# batt_mon_v1.net
KiCad netlist of a schematic drawn in EAGLE
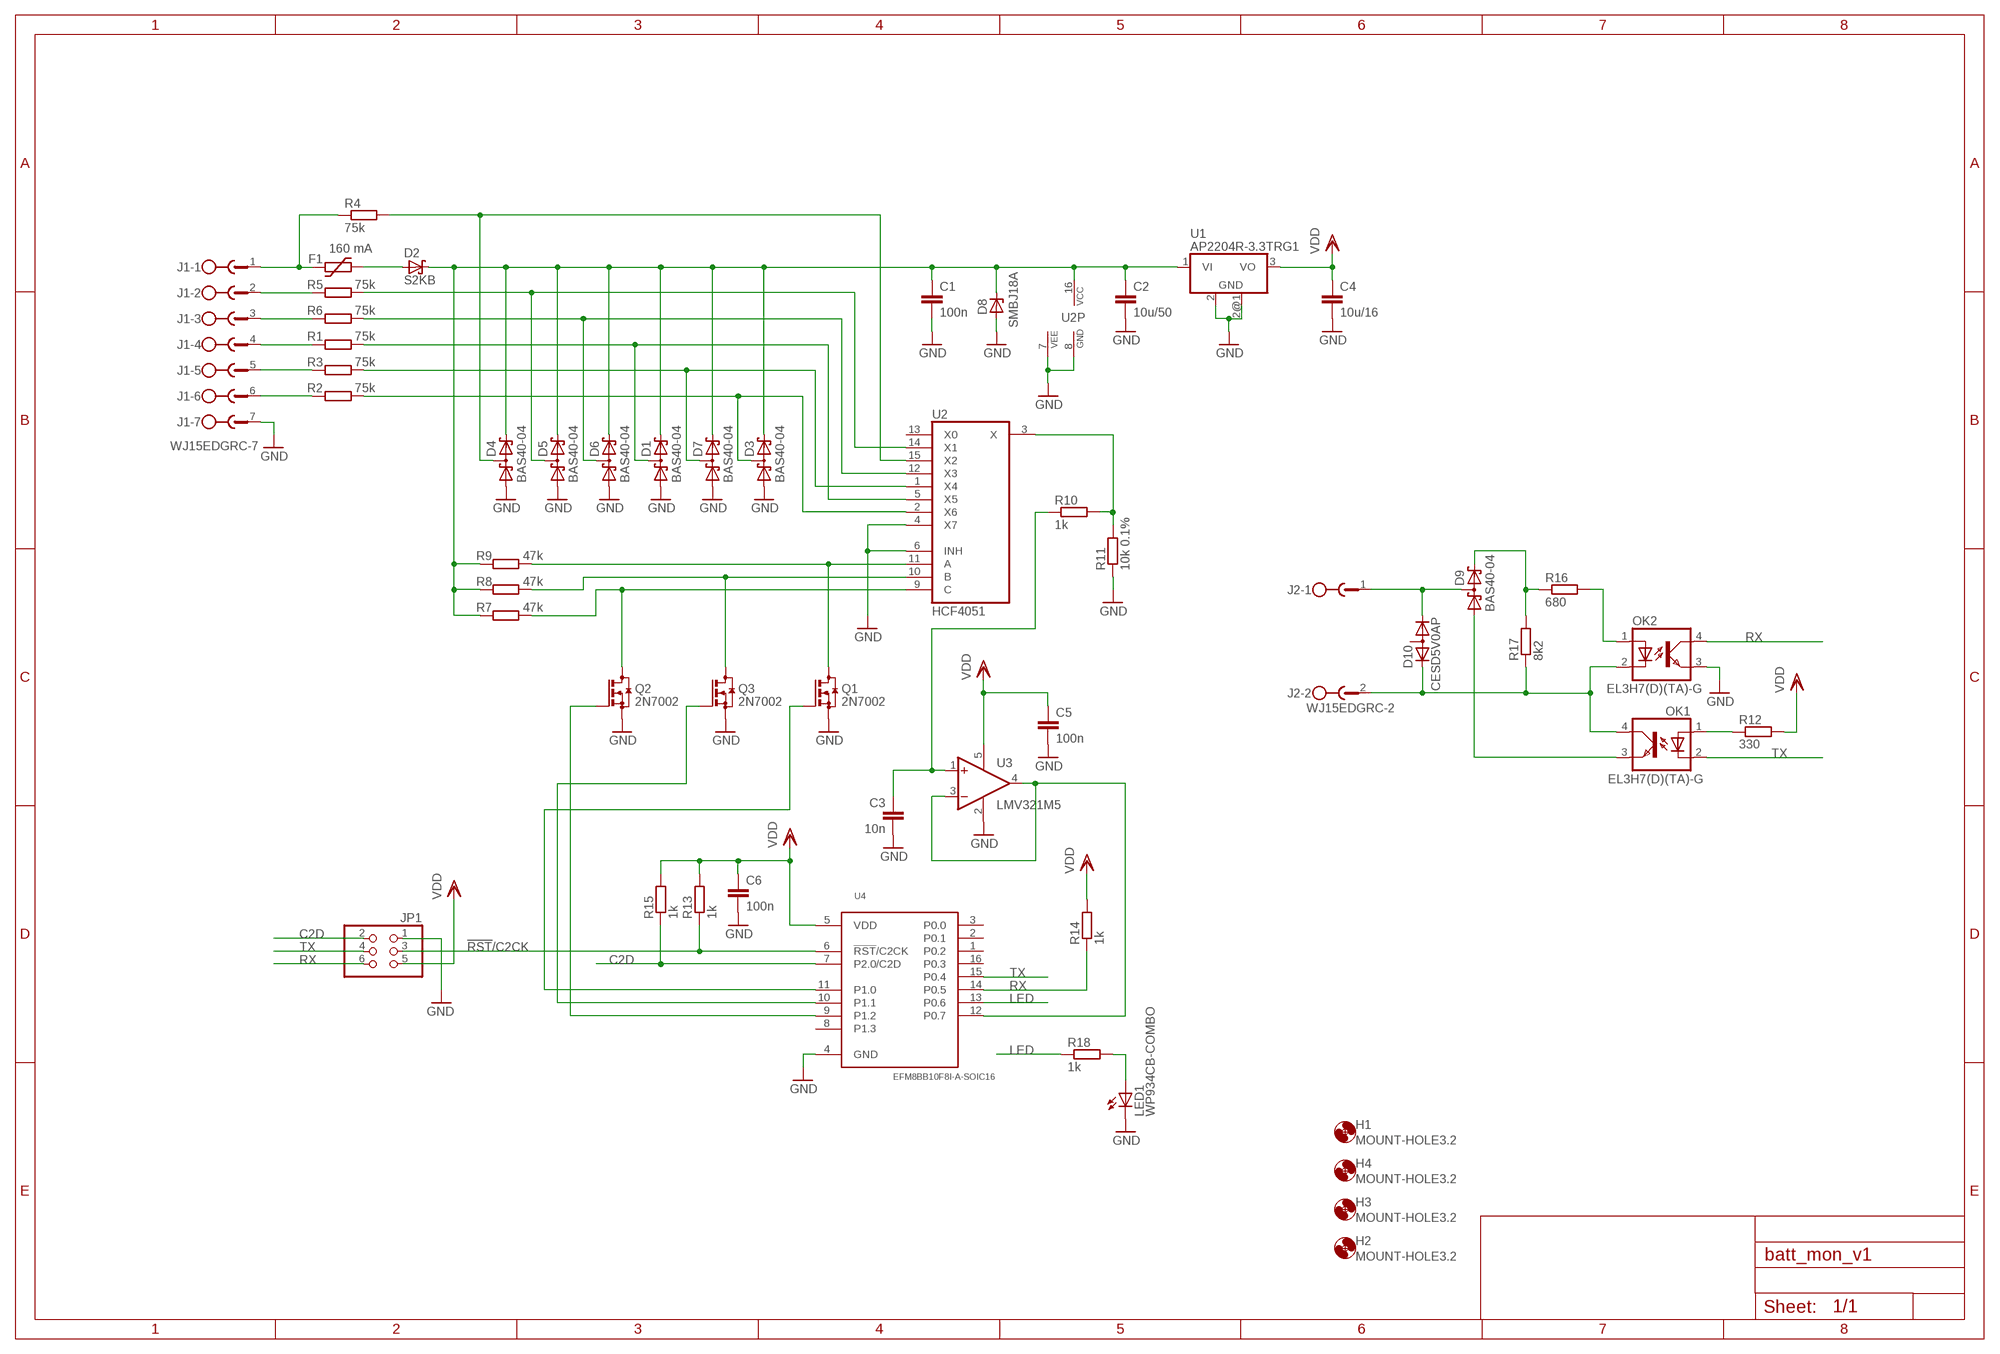
[diagram p0: schematic, sheet 1]

(export (version "E")
  (design (tool "Eeschema 10.0.6"))
  (components
    (comp (ref "C1")
      (value "100n")
      (footprint "eagle-import:C0805")
      (libsource (lib "eagle-import") (part "C-EUC0805"))
    )
    (comp (ref "C2")
      (value "10u/50")
      (footprint "eagle-import:C1206")
      (libsource (lib "eagle-import") (part "C-EUC1206"))
    )
    (comp (ref "C3")
      (value "10n")
      (footprint "eagle-import:C0805")
      (libsource (lib "eagle-import") (part "C-EUC0805"))
    )
    (comp (ref "C4")
      (value "10u/16")
      (footprint "eagle-import:C1206")
      (libsource (lib "eagle-import") (part "C-EUC1206"))
    )
    (comp (ref "C5")
      (value "100n")
      (footprint "eagle-import:C0805")
      (libsource (lib "eagle-import") (part "C-EUC0805"))
    )
    (comp (ref "C6")
      (value "100n")
      (footprint "eagle-import:C0805")
      (libsource (lib "eagle-import") (part "C-EUC0805"))
    )
    (comp (ref "D1")
      (value "BAS40-04")
      (footprint "eagle-import:SOT23")
      (libsource (lib "eagle-import") (part "BAS40-04"))
    )
    (comp (ref "D2")
      (value "S2KB")
      (footprint "eagle-import:SMB")
      (libsource (lib "eagle-import") (part "SCHOTTKY-DIODESMD"))
    )
    (comp (ref "D3")
      (value "BAS40-04")
      (footprint "eagle-import:SOT23")
      (libsource (lib "eagle-import") (part "BAS40-04"))
    )
    (comp (ref "D4")
      (value "BAS40-04")
      (footprint "eagle-import:SOT23")
      (libsource (lib "eagle-import") (part "BAS40-04"))
    )
    (comp (ref "D5")
      (value "BAS40-04")
      (footprint "eagle-import:SOT23")
      (libsource (lib "eagle-import") (part "BAS40-04"))
    )
    (comp (ref "D6")
      (value "BAS40-04")
      (footprint "eagle-import:SOT23")
      (libsource (lib "eagle-import") (part "BAS40-04"))
    )
    (comp (ref "D7")
      (value "BAS40-04")
      (footprint "eagle-import:SOT23")
      (libsource (lib "eagle-import") (part "BAS40-04"))
    )
    (comp (ref "D8")
      (value "SMBJ18A")
      (footprint "eagle-import:SMB")
      (libsource (lib "eagle-import") (part "ZENER-DIODESMB"))
    )
    (comp (ref "D9")
      (value "BAS40-04")
      (footprint "eagle-import:SOT23")
      (libsource (lib "eagle-import") (part "BAS40-04"))
    )
    (comp (ref "D10")
      (value "CESD5V0AP")
      (footprint "eagle-import:SOT23")
      (libsource (lib "eagle-import") (part "DIODE-2CA|ACSOT23"))
    )
    (comp (ref "F1")
      (value "160 mA")
      (footprint "eagle-import:1206L")
      (libsource (lib "eagle-import") (part "1206L"))
    )
    (comp (ref "H1")
      (value "MOUNT-HOLE3.2")
      (footprint "eagle-import:3,2")
      (libsource (lib "eagle-import") (part "MOUNT-HOLE3.2"))
    )
    (comp (ref "H2")
      (value "MOUNT-HOLE3.2")
      (footprint "eagle-import:3,2")
      (libsource (lib "eagle-import") (part "MOUNT-HOLE3.2"))
    )
    (comp (ref "H3")
      (value "MOUNT-HOLE3.2")
      (footprint "eagle-import:3,2")
      (libsource (lib "eagle-import") (part "MOUNT-HOLE3.2"))
    )
    (comp (ref "H4")
      (value "MOUNT-HOLE3.2")
      (footprint "eagle-import:3,2")
      (libsource (lib "eagle-import") (part "MOUNT-HOLE3.2"))
    )
    (comp (ref "J1")
      (value "WJ15EDGRC-7")
      (footprint "eagle-import:WJ15EDGRC-3.81-7")
      (libsource (lib "eagle-import") (part "WJ15EDGRC-7"))
    )
    (comp (ref "J2")
      (value "WJ15EDGRC-2")
      (footprint "eagle-import:WJ15EDGRC-3.81-2")
      (libsource (lib "eagle-import") (part "WJ15EDGRC-2"))
    )
    (comp (ref "JP1")
      (value "PINHD-2X3")
      (footprint "eagle-import:2X03")
      (libsource (lib "eagle-import") (part "PINHD-2X3"))
    )
    (comp (ref "LED1")
      (value "WP934CB-COMBO")
      (footprint "eagle-import:WP934CB-COMBO")
      (libsource (lib "eagle-import") (part "WP934CB-COMBO"))
    )
    (comp (ref "OK1")
      (value "EL3H7(D)(TA)-G")
      (footprint "eagle-import:MINI-FLAT-4")
      (libsource (lib "eagle-import") (part "EL3H7"))
    )
    (comp (ref "OK2")
      (value "EL3H7(D)(TA)-G")
      (footprint "eagle-import:MINI-FLAT-4")
      (libsource (lib "eagle-import") (part "EL3H7"))
    )
    (comp (ref "Q1")
      (value "2N7002")
      (footprint "eagle-import:SOT23")
      (libsource (lib "eagle-import") (part "BSS123"))
    )
    (comp (ref "Q2")
      (value "2N7002")
      (footprint "eagle-import:SOT23")
      (libsource (lib "eagle-import") (part "BSS123"))
    )
    (comp (ref "Q3")
      (value "2N7002")
      (footprint "eagle-import:SOT23")
      (libsource (lib "eagle-import") (part "BSS123"))
    )
    (comp (ref "R1")
      (value "75k")
      (footprint "eagle-import:R1206")
      (libsource (lib "eagle-import") (part "R-EU_R1206"))
    )
    (comp (ref "R2")
      (value "75k")
      (footprint "eagle-import:R1206")
      (libsource (lib "eagle-import") (part "R-EU_R1206"))
    )
    (comp (ref "R3")
      (value "75k")
      (footprint "eagle-import:R1206")
      (libsource (lib "eagle-import") (part "R-EU_R1206"))
    )
    (comp (ref "R4")
      (value "75k")
      (footprint "eagle-import:R1206")
      (libsource (lib "eagle-import") (part "R-EU_R1206"))
    )
    (comp (ref "R5")
      (value "75k")
      (footprint "eagle-import:R1206")
      (libsource (lib "eagle-import") (part "R-EU_R1206"))
    )
    (comp (ref "R6")
      (value "75k")
      (footprint "eagle-import:R1206")
      (libsource (lib "eagle-import") (part "R-EU_R1206"))
    )
    (comp (ref "R7")
      (value "47k")
      (footprint "eagle-import:R0805")
      (libsource (lib "eagle-import") (part "R-EU_R0805"))
    )
    (comp (ref "R8")
      (value "47k")
      (footprint "eagle-import:R0805")
      (libsource (lib "eagle-import") (part "R-EU_R0805"))
    )
    (comp (ref "R9")
      (value "47k")
      (footprint "eagle-import:R0805")
      (libsource (lib "eagle-import") (part "R-EU_R0805"))
    )
    (comp (ref "R10")
      (value "1k")
      (footprint "eagle-import:R0805")
      (libsource (lib "eagle-import") (part "R-EU_R0805"))
    )
    (comp (ref "R11")
      (value "10k 0.1%")
      (footprint "eagle-import:R0805")
      (libsource (lib "eagle-import") (part "R-EU_R0805"))
    )
    (comp (ref "R12")
      (value "330")
      (footprint "eagle-import:R0805")
      (libsource (lib "eagle-import") (part "R-EU_R0805"))
    )
    (comp (ref "R13")
      (value "1k")
      (footprint "eagle-import:R0805")
      (libsource (lib "eagle-import") (part "R-EU_R0805"))
    )
    (comp (ref "R14")
      (value "1k")
      (footprint "eagle-import:R0805")
      (libsource (lib "eagle-import") (part "R-EU_R0805"))
    )
    (comp (ref "R15")
      (value "1k")
      (footprint "eagle-import:R0805")
      (libsource (lib "eagle-import") (part "R-EU_R0805"))
    )
    (comp (ref "R16")
      (value "680")
      (footprint "eagle-import:R0805")
      (libsource (lib "eagle-import") (part "R-EU_R0805"))
    )
    (comp (ref "R17")
      (value "8k2")
      (footprint "eagle-import:R0805")
      (libsource (lib "eagle-import") (part "R-EU_R0805"))
    )
    (comp (ref "R18")
      (value "1k")
      (footprint "eagle-import:R0805")
      (libsource (lib "eagle-import") (part "R-EU_R0805"))
    )
    (comp (ref "U1")
      (value "AP2204R-3.3TRG1")
      (footprint "eagle-import:SOT89")
      (libsource (lib "eagle-import") (part "MCP1754MB33"))
    )
    (comp (ref "U2")
      (value "HCF4051")
      (footprint "eagle-import:SO16")
      (libsource (lib "eagle-import") (part "4051D"))
    )
    (comp (ref "U3")
      (value "LMV321M5")
      (footprint "eagle-import:SOT23-5")
      (libsource (lib "eagle-import") (part "LMV321?M5"))
    )
    (comp (ref "U4")
      (value "EFM8BB10F8I-A-SOIC16")
      (footprint "eagle-import:SO16")
      (libsource (lib "eagle-import") (part "EFM8BB1"))
    )
  )
  (nets
    (net (code "1") (name "/C2D") (class "Default")
      (node (ref "JP1") (pin "2") (pinfunction "2_2") (pintype "passive"))
      (node (ref "R15") (pin "1") (pinfunction "1_1") (pintype "passive"))
      (node (ref "U4") (pin "7") (pinfunction "P2.0/C2D_7") (pintype "bidirectional"))
    )
    (net (code "2") (name "/LED") (class "Default")
      (node (ref "R18") (pin "1") (pinfunction "1_1") (pintype "passive"))
      (node (ref "U4") (pin "13") (pinfunction "P0.6_13") (pintype "bidirectional"))
    )
    (net (code "3") (name "/RX") (class "Default")
      (node (ref "JP1") (pin "6") (pinfunction "6_6") (pintype "passive"))
      (node (ref "OK2") (pin "4") (pinfunction "COL_4") (pintype "passive"))
      (node (ref "R14") (pin "1") (pinfunction "1_1") (pintype "passive"))
      (node (ref "U4") (pin "14") (pinfunction "P0.5_14") (pintype "bidirectional"))
    )
    (net (code "4") (name "/TX") (class "Default")
      (node (ref "JP1") (pin "4") (pinfunction "4_4") (pintype "passive"))
      (node (ref "OK1") (pin "2") (pinfunction "C_2") (pintype "passive"))
      (node (ref "U4") (pin "15") (pinfunction "P0.4_15") (pintype "bidirectional"))
    )
    (net (code "5") (name "/~{RST}{slash}C2CK") (class "Default")
      (node (ref "JP1") (pin "3") (pinfunction "3_3") (pintype "passive"))
      (node (ref "R13") (pin "1") (pinfunction "1_1") (pintype "passive"))
      (node (ref "U4") (pin "6") (pinfunction "~{RST}/C2CK_6") (pintype "bidirectional"))
    )
    (net (code "6") (name "GND") (class "Default")
      (node (ref "C1") (pin "2") (pinfunction "2_2") (pintype "passive"))
      (node (ref "C2") (pin "2") (pinfunction "2_2") (pintype "passive"))
      (node (ref "C3") (pin "2") (pinfunction "2_2") (pintype "passive"))
      (node (ref "C4") (pin "2") (pinfunction "2_2") (pintype "passive"))
      (node (ref "C5") (pin "2") (pinfunction "2_2") (pintype "passive"))
      (node (ref "C6") (pin "2") (pinfunction "2_2") (pintype "passive"))
      (node (ref "D1") (pin "1") (pinfunction "A1_1") (pintype "passive"))
      (node (ref "D3") (pin "1") (pinfunction "A1_1") (pintype "passive"))
      (node (ref "D4") (pin "1") (pinfunction "A1_1") (pintype "passive"))
      (node (ref "D5") (pin "1") (pinfunction "A1_1") (pintype "passive"))
      (node (ref "D6") (pin "1") (pinfunction "A1_1") (pintype "passive"))
      (node (ref "D7") (pin "1") (pinfunction "A1_1") (pintype "passive"))
      (node (ref "D8") (pin "A") (pinfunction "A_A") (pintype "passive"))
      (node (ref "J1") (pin "7") (pinfunction "1_7") (pintype "passive"))
      (node (ref "JP1") (pin "1") (pinfunction "1_1") (pintype "passive"))
      (node (ref "LED1") (pin "K") (pinfunction "C_K") (pintype "passive"))
      (node (ref "LED1") (pin "K1") (pinfunction "C_K1") (pintype "passive"))
      (node (ref "OK2") (pin "3") (pinfunction "EMIT_3") (pintype "passive"))
      (node (ref "Q1") (pin "2") (pinfunction "S_2") (pintype "passive"))
      (node (ref "Q2") (pin "2") (pinfunction "S_2") (pintype "passive"))
      (node (ref "Q3") (pin "2") (pinfunction "S_2") (pintype "passive"))
      (node (ref "R11") (pin "1") (pinfunction "1_1") (pintype "passive"))
      (node (ref "U1") (pin "2") (pinfunction "GND_2") (pintype "passive"))
      (node (ref "U1") (pin "2@1") (pinfunction "GND_2@1") (pintype "passive"))
      (node (ref "U2") (pin "4") (pinfunction "X7_4") (pintype "bidirectional"))
      (node (ref "U2") (pin "6") (pinfunction "INH_6") (pintype "input"))
      (node (ref "U2") (pin "7") (pinfunction "VEE_7") (pintype "power_in"))
      (node (ref "U2") (pin "8") (pinfunction "GND_8") (pintype "power_in"))
      (node (ref "U3") (pin "2") (pinfunction "V-_2") (pintype "power_in"))
      (node (ref "U4") (pin "4") (pinfunction "GND_4") (pintype "bidirectional"))
    )
    (net (code "7") (name "Net-(D1-C1A2)") (class "Default")
      (node (ref "D1") (pin "3") (pinfunction "C1A2_3") (pintype "passive"))
      (node (ref "R1") (pin "2") (pinfunction "2_2") (pintype "passive"))
      (node (ref "U2") (pin "5") (pinfunction "X5_5") (pintype "bidirectional"))
    )
    (net (code "8") (name "Net-(D1-C2)") (class "Default")
      (node (ref "C1") (pin "1") (pinfunction "1_1") (pintype "passive"))
      (node (ref "C2") (pin "1") (pinfunction "1_1") (pintype "passive"))
      (node (ref "D1") (pin "2") (pinfunction "C2_2") (pintype "passive"))
      (node (ref "D2") (pin "C") (pinfunction "C_C") (pintype "passive"))
      (node (ref "D3") (pin "2") (pinfunction "C2_2") (pintype "passive"))
      (node (ref "D4") (pin "2") (pinfunction "C2_2") (pintype "passive"))
      (node (ref "D5") (pin "2") (pinfunction "C2_2") (pintype "passive"))
      (node (ref "D6") (pin "2") (pinfunction "C2_2") (pintype "passive"))
      (node (ref "D7") (pin "2") (pinfunction "C2_2") (pintype "passive"))
      (node (ref "D8") (pin "C") (pinfunction "C_C") (pintype "passive"))
      (node (ref "R7") (pin "1") (pinfunction "1_1") (pintype "passive"))
      (node (ref "R8") (pin "1") (pinfunction "1_1") (pintype "passive"))
      (node (ref "R9") (pin "1") (pinfunction "1_1") (pintype "passive"))
      (node (ref "U1") (pin "1") (pinfunction "VI_1") (pintype "input"))
      (node (ref "U2") (pin "16") (pinfunction "VCC_16") (pintype "power_in"))
    )
    (net (code "9") (name "Net-(D3-C1A2)") (class "Default")
      (node (ref "D3") (pin "3") (pinfunction "C1A2_3") (pintype "passive"))
      (node (ref "R2") (pin "2") (pinfunction "2_2") (pintype "passive"))
      (node (ref "U2") (pin "2") (pinfunction "X6_2") (pintype "bidirectional"))
    )
    (net (code "10") (name "Net-(D4-C1A2)") (class "Default")
      (node (ref "D4") (pin "3") (pinfunction "C1A2_3") (pintype "passive"))
      (node (ref "R4") (pin "2") (pinfunction "2_2") (pintype "passive"))
      (node (ref "U2") (pin "15") (pinfunction "X2_15") (pintype "bidirectional"))
    )
    (net (code "11") (name "Net-(D5-C1A2)") (class "Default")
      (node (ref "D5") (pin "3") (pinfunction "C1A2_3") (pintype "passive"))
      (node (ref "R5") (pin "2") (pinfunction "2_2") (pintype "passive"))
      (node (ref "U2") (pin "14") (pinfunction "X1_14") (pintype "bidirectional"))
    )
    (net (code "12") (name "Net-(D6-C1A2)") (class "Default")
      (node (ref "D6") (pin "3") (pinfunction "C1A2_3") (pintype "passive"))
      (node (ref "R6") (pin "2") (pinfunction "2_2") (pintype "passive"))
      (node (ref "U2") (pin "12") (pinfunction "X3_12") (pintype "bidirectional"))
    )
    (net (code "13") (name "Net-(D7-C1A2)") (class "Default")
      (node (ref "D7") (pin "3") (pinfunction "C1A2_3") (pintype "passive"))
      (node (ref "R3") (pin "2") (pinfunction "2_2") (pintype "passive"))
      (node (ref "U2") (pin "1") (pinfunction "X4_1") (pintype "bidirectional"))
    )
    (net (code "14") (name "Net-(D9-A1)") (class "Default")
      (node (ref "D9") (pin "1") (pinfunction "A1_1") (pintype "passive"))
      (node (ref "OK1") (pin "3") (pinfunction "EMIT_3") (pintype "passive"))
    )
    (net (code "15") (name "Net-(D9-C2)") (class "Default")
      (node (ref "D9") (pin "2") (pinfunction "C2_2") (pintype "passive"))
      (node (ref "R16") (pin "1") (pinfunction "1_1") (pintype "passive"))
      (node (ref "R17") (pin "2") (pinfunction "2_2") (pintype "passive"))
    )
    (net (code "16") (name "Net-(D10-K1)") (class "Default")
      (node (ref "D10") (pin "1") (pinfunction "K1_1") (pintype "passive"))
      (node (ref "D9") (pin "3") (pinfunction "C1A2_3") (pintype "passive"))
      (node (ref "J2") (pin "1") (pinfunction "1_1") (pintype "passive"))
    )
    (net (code "17") (name "Net-(D10-K2)") (class "Default")
      (node (ref "D10") (pin "2") (pinfunction "K2_2") (pintype "passive"))
      (node (ref "J2") (pin "2") (pinfunction "1_2") (pintype "passive"))
      (node (ref "OK1") (pin "4") (pinfunction "COL_4") (pintype "passive"))
      (node (ref "OK2") (pin "2") (pinfunction "C_2") (pintype "passive"))
      (node (ref "R17") (pin "1") (pinfunction "1_1") (pintype "passive"))
    )
    (net (code "18") (name "Net-(F1-1)") (class "Default")
      (node (ref "F1") (pin "P$1") (pinfunction "1_P$1") (pintype "passive"))
      (node (ref "J1") (pin "1") (pinfunction "1_1") (pintype "passive"))
      (node (ref "R4") (pin "1") (pinfunction "1_1") (pintype "passive"))
    )
    (net (code "19") (name "Net-(F1-2)") (class "Default")
      (node (ref "D2") (pin "A") (pinfunction "A_A") (pintype "passive"))
      (node (ref "F1") (pin "P$2") (pinfunction "2_P$2") (pintype "passive"))
    )
    (net (code "20") (name "Net-(J1B-1)") (class "Default")
      (node (ref "J1") (pin "2") (pinfunction "1_2") (pintype "passive"))
      (node (ref "R5") (pin "1") (pinfunction "1_1") (pintype "passive"))
    )
    (net (code "21") (name "Net-(J1C-1)") (class "Default")
      (node (ref "J1") (pin "3") (pinfunction "1_3") (pintype "passive"))
      (node (ref "R6") (pin "1") (pinfunction "1_1") (pintype "passive"))
    )
    (net (code "22") (name "Net-(J1D-1)") (class "Default")
      (node (ref "J1") (pin "4") (pinfunction "1_4") (pintype "passive"))
      (node (ref "R1") (pin "1") (pinfunction "1_1") (pintype "passive"))
    )
    (net (code "23") (name "Net-(J1E-1)") (class "Default")
      (node (ref "J1") (pin "5") (pinfunction "1_5") (pintype "passive"))
      (node (ref "R3") (pin "1") (pinfunction "1_1") (pintype "passive"))
    )
    (net (code "24") (name "Net-(J1F-1)") (class "Default")
      (node (ref "J1") (pin "6") (pinfunction "1_6") (pintype "passive"))
      (node (ref "R2") (pin "1") (pinfunction "1_1") (pintype "passive"))
    )
    (net (code "25") (name "Net-(LED1-A-PadA1)") (class "Default")
      (node (ref "LED1") (pin "A") (pinfunction "A_A") (pintype "passive"))
      (node (ref "LED1") (pin "A1") (pinfunction "A_A1") (pintype "passive"))
      (node (ref "R18") (pin "2") (pinfunction "2_2") (pintype "passive"))
    )
    (net (code "26") (name "Net-(OK1-A)") (class "Default")
      (node (ref "OK1") (pin "1") (pinfunction "A_1") (pintype "passive"))
      (node (ref "R12") (pin "1") (pinfunction "1_1") (pintype "passive"))
    )
    (net (code "27") (name "Net-(OK2-A)") (class "Default")
      (node (ref "OK2") (pin "1") (pinfunction "A_1") (pintype "passive"))
      (node (ref "R16") (pin "2") (pinfunction "2_2") (pintype "passive"))
    )
    (net (code "28") (name "Net-(Q1-D)") (class "Default")
      (node (ref "Q1") (pin "3") (pinfunction "D_3") (pintype "passive"))
      (node (ref "R9") (pin "2") (pinfunction "2_2") (pintype "passive"))
      (node (ref "U2") (pin "11") (pinfunction "A_11") (pintype "input"))
    )
    (net (code "29") (name "Net-(Q1-G)") (class "Default")
      (node (ref "Q1") (pin "1") (pinfunction "G_1") (pintype "passive"))
      (node (ref "U4") (pin "11") (pinfunction "P1.0_11") (pintype "bidirectional"))
    )
    (net (code "30") (name "Net-(Q2-D)") (class "Default")
      (node (ref "Q2") (pin "3") (pinfunction "D_3") (pintype "passive"))
      (node (ref "R7") (pin "2") (pinfunction "2_2") (pintype "passive"))
      (node (ref "U2") (pin "9") (pinfunction "C_9") (pintype "input"))
    )
    (net (code "31") (name "Net-(Q2-G)") (class "Default")
      (node (ref "Q2") (pin "1") (pinfunction "G_1") (pintype "passive"))
      (node (ref "U4") (pin "9") (pinfunction "P1.2_9") (pintype "bidirectional"))
    )
    (net (code "32") (name "Net-(Q3-D)") (class "Default")
      (node (ref "Q3") (pin "3") (pinfunction "D_3") (pintype "passive"))
      (node (ref "R8") (pin "2") (pinfunction "2_2") (pintype "passive"))
      (node (ref "U2") (pin "10") (pinfunction "B_10") (pintype "input"))
    )
    (net (code "33") (name "Net-(Q3-G)") (class "Default")
      (node (ref "Q3") (pin "1") (pinfunction "G_1") (pintype "passive"))
      (node (ref "U4") (pin "10") (pinfunction "P1.1_10") (pintype "bidirectional"))
    )
    (net (code "34") (name "Net-(U2A-X)") (class "Default")
      (node (ref "R10") (pin "2") (pinfunction "2_2") (pintype "passive"))
      (node (ref "R11") (pin "2") (pinfunction "2_2") (pintype "passive"))
      (node (ref "U2") (pin "3") (pinfunction "X_3") (pintype "bidirectional"))
    )
    (net (code "35") (name "Net-(U3-+IN)") (class "Default")
      (node (ref "C3") (pin "1") (pinfunction "1_1") (pintype "passive"))
      (node (ref "R10") (pin "1") (pinfunction "1_1") (pintype "passive"))
      (node (ref "U3") (pin "1") (pinfunction "+IN_1") (pintype "input"))
    )
    (net (code "36") (name "Net-(U3--IN)") (class "Default")
      (node (ref "U3") (pin "3") (pinfunction "-IN_3") (pintype "input"))
      (node (ref "U3") (pin "4") (pinfunction "OUT_4") (pintype "output"))
      (node (ref "U4") (pin "12") (pinfunction "P0.7_12") (pintype "bidirectional"))
    )
    (net (code "37") (name "VDD") (class "Default")
      (node (ref "C4") (pin "1") (pinfunction "1_1") (pintype "passive"))
      (node (ref "C5") (pin "1") (pinfunction "1_1") (pintype "passive"))
      (node (ref "C6") (pin "1") (pinfunction "1_1") (pintype "passive"))
      (node (ref "JP1") (pin "5") (pinfunction "5_5") (pintype "passive"))
      (node (ref "R12") (pin "2") (pinfunction "2_2") (pintype "passive"))
      (node (ref "R13") (pin "2") (pinfunction "2_2") (pintype "passive"))
      (node (ref "R14") (pin "2") (pinfunction "2_2") (pintype "passive"))
      (node (ref "R15") (pin "2") (pinfunction "2_2") (pintype "passive"))
      (node (ref "U1") (pin "3") (pinfunction "VO_3") (pintype "passive"))
      (node (ref "U3") (pin "5") (pinfunction "V+_5") (pintype "power_in"))
      (node (ref "U4") (pin "5") (pinfunction "VDD_5") (pintype "bidirectional"))
    )
    (net (code "38") (name "unconnected-(D10-A-Pad3)") (class "Default")
      (node (ref "D10") (pin "3") (pinfunction "A_3") (pintype "passive"))
    )
    (net (code "39") (name "unconnected-(U2A-X0-Pad13)") (class "Default")
      (node (ref "U2") (pin "13") (pinfunction "X0_13") (pintype "bidirectional"))
    )
    (net (code "40") (name "unconnected-(U4-P0.0-Pad3)") (class "Default")
      (node (ref "U4") (pin "3") (pinfunction "P0.0_3") (pintype "bidirectional"))
    )
    (net (code "41") (name "unconnected-(U4-P0.1-Pad2)") (class "Default")
      (node (ref "U4") (pin "2") (pinfunction "P0.1_2") (pintype "bidirectional"))
    )
    (net (code "42") (name "unconnected-(U4-P0.2-Pad1)") (class "Default")
      (node (ref "U4") (pin "1") (pinfunction "P0.2_1") (pintype "bidirectional"))
    )
    (net (code "43") (name "unconnected-(U4-P0.3-Pad16)") (class "Default")
      (node (ref "U4") (pin "16") (pinfunction "P0.3_16") (pintype "bidirectional"))
    )
    (net (code "44") (name "unconnected-(U4-P1.3-Pad8)") (class "Default")
      (node (ref "U4") (pin "8") (pinfunction "P1.3_8") (pintype "bidirectional"))
    )
  )
)
